# hwcb_2.net
KiCad netlist of a schematic drawn in Altium Designer
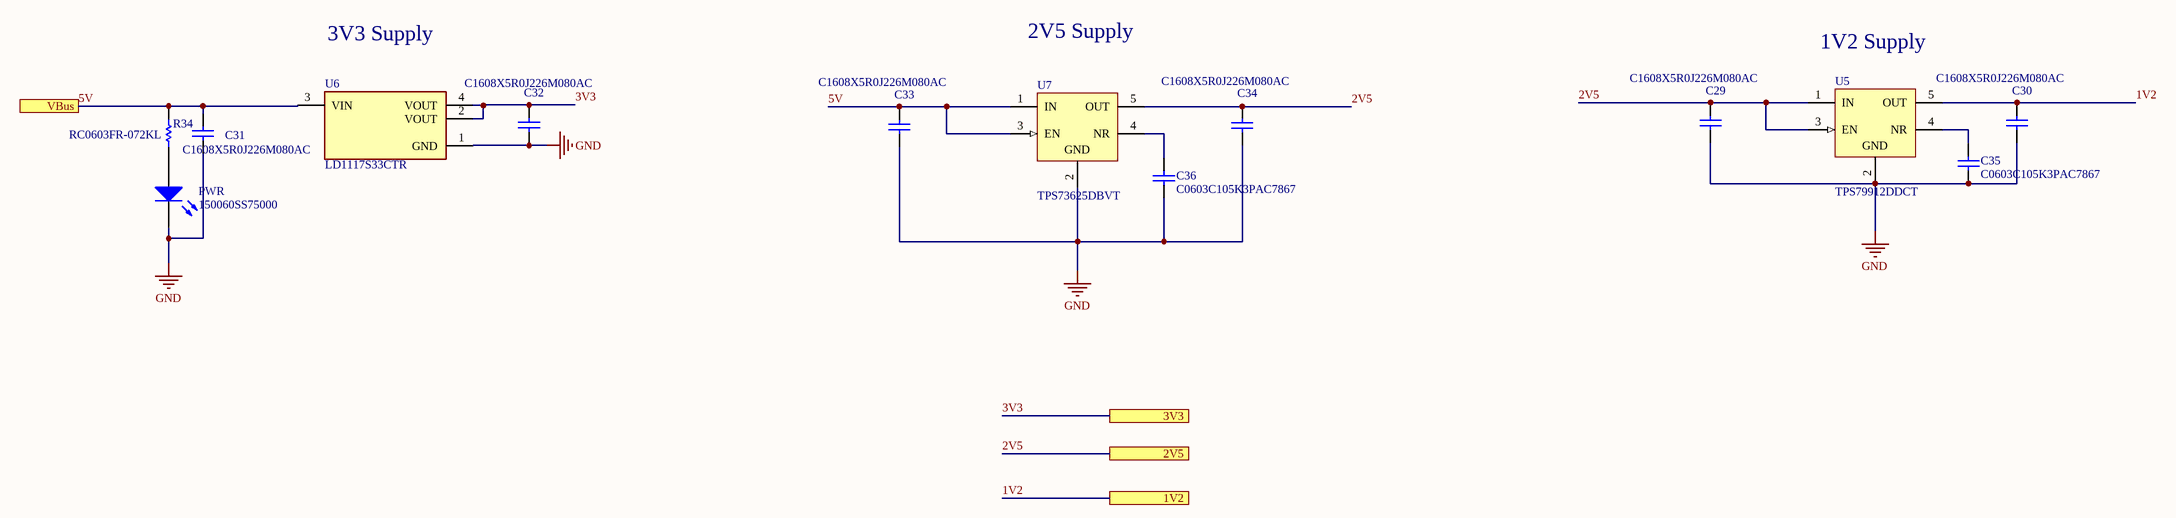
[diagram p0: hwcb_2.SchDoc]

(export (version "E")
  (design (tool "Eeschema 10.0.6"))
  (components
    (comp (ref "C29")
      (value "C1608X5R0J226M080AC")
      (footprint "CAPC1608X100X20ML10")
      (description "Chip Capacitor, 22 uF, +/- 20%, 6.3 V, -55 to 85 degC, 1608 (0603 Metric), RoHS, Tape and Reel")
      (fields
        (field (name "TOLERANCE") "±20%")
        (field (name "PCN PART NUMBER") "MLCCPartNumberChange30/Nov/2012")
      )
      (libsource (lib "Altium Content Vault") (part "CAP-NP-2"))
    )
    (comp (ref "C30")
      (value "C1608X5R0J226M080AC")
      (footprint "CAPC1608X100X20ML10")
      (description "Chip Capacitor, 22 uF, +/- 20%, 6.3 V, -55 to 85 degC, 1608 (0603 Metric), RoHS, Tape and Reel")
      (fields
        (field (name "TOLERANCE") "±20%")
        (field (name "PCN PART NUMBER") "MLCCPartNumberChange30/Nov/2012")
      )
      (libsource (lib "Altium Content Vault") (part "CAP-NP-2"))
    )
    (comp (ref "C31")
      (value "C1608X5R0J226M080AC")
      (footprint "CAPC1608X100X20ML10")
      (description "Chip Capacitor, 22 uF, +/- 20%, 6.3 V, -55 to 85 degC, 1608 (0603 Metric), RoHS, Tape and Reel")
      (fields
        (field (name "TOLERANCE") "±20%")
        (field (name "PCN PART NUMBER") "MLCCPartNumberChange30/Nov/2012")
      )
      (libsource (lib "Altium Content Vault") (part "CAP-NP-2"))
    )
    (comp (ref "C32")
      (value "C1608X5R0J226M080AC")
      (footprint "CAPC1608X100X20ML10")
      (description "Chip Capacitor, 22 uF, +/- 20%, 6.3 V, -55 to 85 degC, 1608 (0603 Metric), RoHS, Tape and Reel")
      (fields
        (field (name "TOLERANCE") "±20%")
        (field (name "PCN PART NUMBER") "MLCCPartNumberChange30/Nov/2012")
      )
      (libsource (lib "Altium Content Vault") (part "CAP-NP-2"))
    )
    (comp (ref "C33")
      (value "C1608X5R0J226M080AC")
      (footprint "CAPC1608X100X20ML10")
      (description "Chip Capacitor, 22 uF, +/- 20%, 6.3 V, -55 to 85 degC, 1608 (0603 Metric), RoHS, Tape and Reel")
      (fields
        (field (name "TOLERANCE") "±20%")
        (field (name "PCN PART NUMBER") "MLCCPartNumberChange30/Nov/2012")
      )
      (libsource (lib "Altium Content Vault") (part "CAP-NP-2"))
    )
    (comp (ref "C34")
      (value "C1608X5R0J226M080AC")
      (footprint "CAPC1608X100X20ML10")
      (description "Chip Capacitor, 22 uF, +/- 20%, 6.3 V, -55 to 85 degC, 1608 (0603 Metric), RoHS, Tape and Reel")
      (fields
        (field (name "TOLERANCE") "±20%")
        (field (name "PCN PART NUMBER") "MLCCPartNumberChange30/Nov/2012")
      )
      (libsource (lib "Altium Content Vault") (part "CAP-NP-2"))
    )
    (comp (ref "C35")
      (value "C0603C105K3PAC7867")
      (footprint "CAPC1608X90X35LL15T15")
      (fields (field (name "MANUFACTURER") "Kemet"))
      (libsource (lib "Altium Content Vault") (part "CAP"))
    )
    (comp (ref "C36")
      (value "C0603C105K3PAC7867")
      (footprint "CAPC1608X90X35LL15T15")
      (fields (field (name "MANUFACTURER") "Kemet"))
      (libsource (lib "Altium Content Vault") (part "CAP"))
    )
    (comp (ref "PWR")
      (value "150060SS75000")
      (footprint "0603_A")
      (description "SMD mono-color Chip LED, WL-SMCW, Super Red")
      (fields (field (name "MANUFACTURER") "Wuerth Elektronik"))
      (libsource (lib "Altium Content Vault") (part "WE-LED_K1A2-2"))
    )
    (comp (ref "R34")
      (value "RC0603FR-072KL")
      (footprint "RESC1608X55X25LL10T15")
      (description "Chip Resistor, 2 KOhm, +/- 1%, 50 V, -55 to 155 degC, 0603 (1608 Metric), RoHS, Tape and Reel")
      (fields (field (name "TOLERANCE") "±1%") (field (name "MANUFACTURER") "Yageo"))
      (libsource (lib "Altium Content Vault") (part "RES-2"))
    )
    (comp (ref "U5")
      (value "TPS79912DDCT")
      (footprint "DDC0005A_L")
      (fields (field (name "MANUFACTURER") "Texas Instruments"))
      (libsource (lib "Altium Content Vault") (part "TI-TPS79NXX-YYSOT5"))
    )
    (comp (ref "U6")
      (value "LD1117S33CTR")
      (footprint "FP-SOT-223-0046067_14-MFG")
      (description "IC REG LINEAR 3.3V 800MA SOT223")
      (libsource (lib "Altium Content Vault") (part "7818869c5c16ceab15634627166a29d"))
    )
    (comp (ref "U7")
      (value "TPS73625DBVT")
      (footprint "DBV0005A_M")
      (fields (field (name "MANUFACTURER") "Texas Instruments"))
      (libsource (lib "Altium Content Vault") (part "TI-TPS79NXX-YYSOT5"))
    )
  )
  (nets
    (net (code "1") (name "/1V2") (class "Default")
      (node (ref "C30") (pin "2") (pinfunction "2_2") (pintype "passive"))
      (node (ref "U5") (pin "5") (pinfunction "OUT_5") (pintype "power_in"))
    )
    (net (code "2") (name "/2V5") (class "Default")
      (node (ref "C29") (pin "2") (pinfunction "2_2") (pintype "passive"))
      (node (ref "C34") (pin "2") (pinfunction "2_2") (pintype "passive"))
      (node (ref "U5") (pin "1") (pinfunction "IN_1") (pintype "power_in"))
      (node (ref "U5") (pin "3") (pinfunction "EN_3") (pintype "input"))
      (node (ref "U7") (pin "5") (pinfunction "OUT_5") (pintype "power_in"))
    )
    (net (code "3") (name "/3V3") (class "Default")
      (node (ref "C32") (pin "2") (pinfunction "2_2") (pintype "passive"))
      (node (ref "U6") (pin "2") (pinfunction "VOUT_2") (pintype "power_in"))
      (node (ref "U6") (pin "4") (pinfunction "VOUT_4") (pintype "power_in"))
    )
    (net (code "4") (name "/5V") (class "Default")
      (node (ref "C31") (pin "2") (pinfunction "2_2") (pintype "passive"))
      (node (ref "C33") (pin "2") (pinfunction "2_2") (pintype "passive"))
      (node (ref "R34") (pin "1") (pinfunction "1_1") (pintype "passive"))
      (node (ref "U6") (pin "3") (pinfunction "VIN_3") (pintype "power_in"))
      (node (ref "U7") (pin "1") (pinfunction "IN_1") (pintype "power_in"))
      (node (ref "U7") (pin "3") (pinfunction "EN_3") (pintype "input"))
    )
    (net (code "5") (name "GND") (class "Default")
      (node (ref "C29") (pin "1") (pinfunction "1_1") (pintype "passive"))
      (node (ref "C30") (pin "1") (pinfunction "1_1") (pintype "passive"))
      (node (ref "C31") (pin "1") (pinfunction "1_1") (pintype "passive"))
      (node (ref "C32") (pin "1") (pinfunction "1_1") (pintype "passive"))
      (node (ref "C33") (pin "1") (pinfunction "1_1") (pintype "passive"))
      (node (ref "C34") (pin "1") (pinfunction "1_1") (pintype "passive"))
      (node (ref "C35") (pin "2") (pinfunction "2_2") (pintype "passive"))
      (node (ref "C36") (pin "2") (pinfunction "2_2") (pintype "passive"))
      (node (ref "PWR") (pin "1") (pinfunction "K_1") (pintype "passive"))
      (node (ref "U5") (pin "2") (pinfunction "GND_2") (pintype "power_in"))
      (node (ref "U6") (pin "1") (pinfunction "GND_1") (pintype "power_in"))
      (node (ref "U7") (pin "2") (pinfunction "GND_2") (pintype "power_in"))
    )
    (net (code "6") (name "Net-(PWR-A)") (class "Default")
      (node (ref "PWR") (pin "2") (pinfunction "A_2") (pintype "passive"))
      (node (ref "R34") (pin "2") (pinfunction "2_2") (pintype "passive"))
    )
    (net (code "7") (name "Net-(U5-NR)") (class "Default")
      (node (ref "C35") (pin "1") (pinfunction "1_1") (pintype "passive"))
      (node (ref "U5") (pin "4") (pinfunction "NR_4") (pintype "passive"))
    )
    (net (code "8") (name "Net-(U7-NR)") (class "Default")
      (node (ref "C36") (pin "1") (pinfunction "1_1") (pintype "passive"))
      (node (ref "U7") (pin "4") (pinfunction "NR_4") (pintype "passive"))
    )
  )
)
